# Opto_sensor_Comperator.net
KiCad netlist of a schematic drawn in EasyEDA
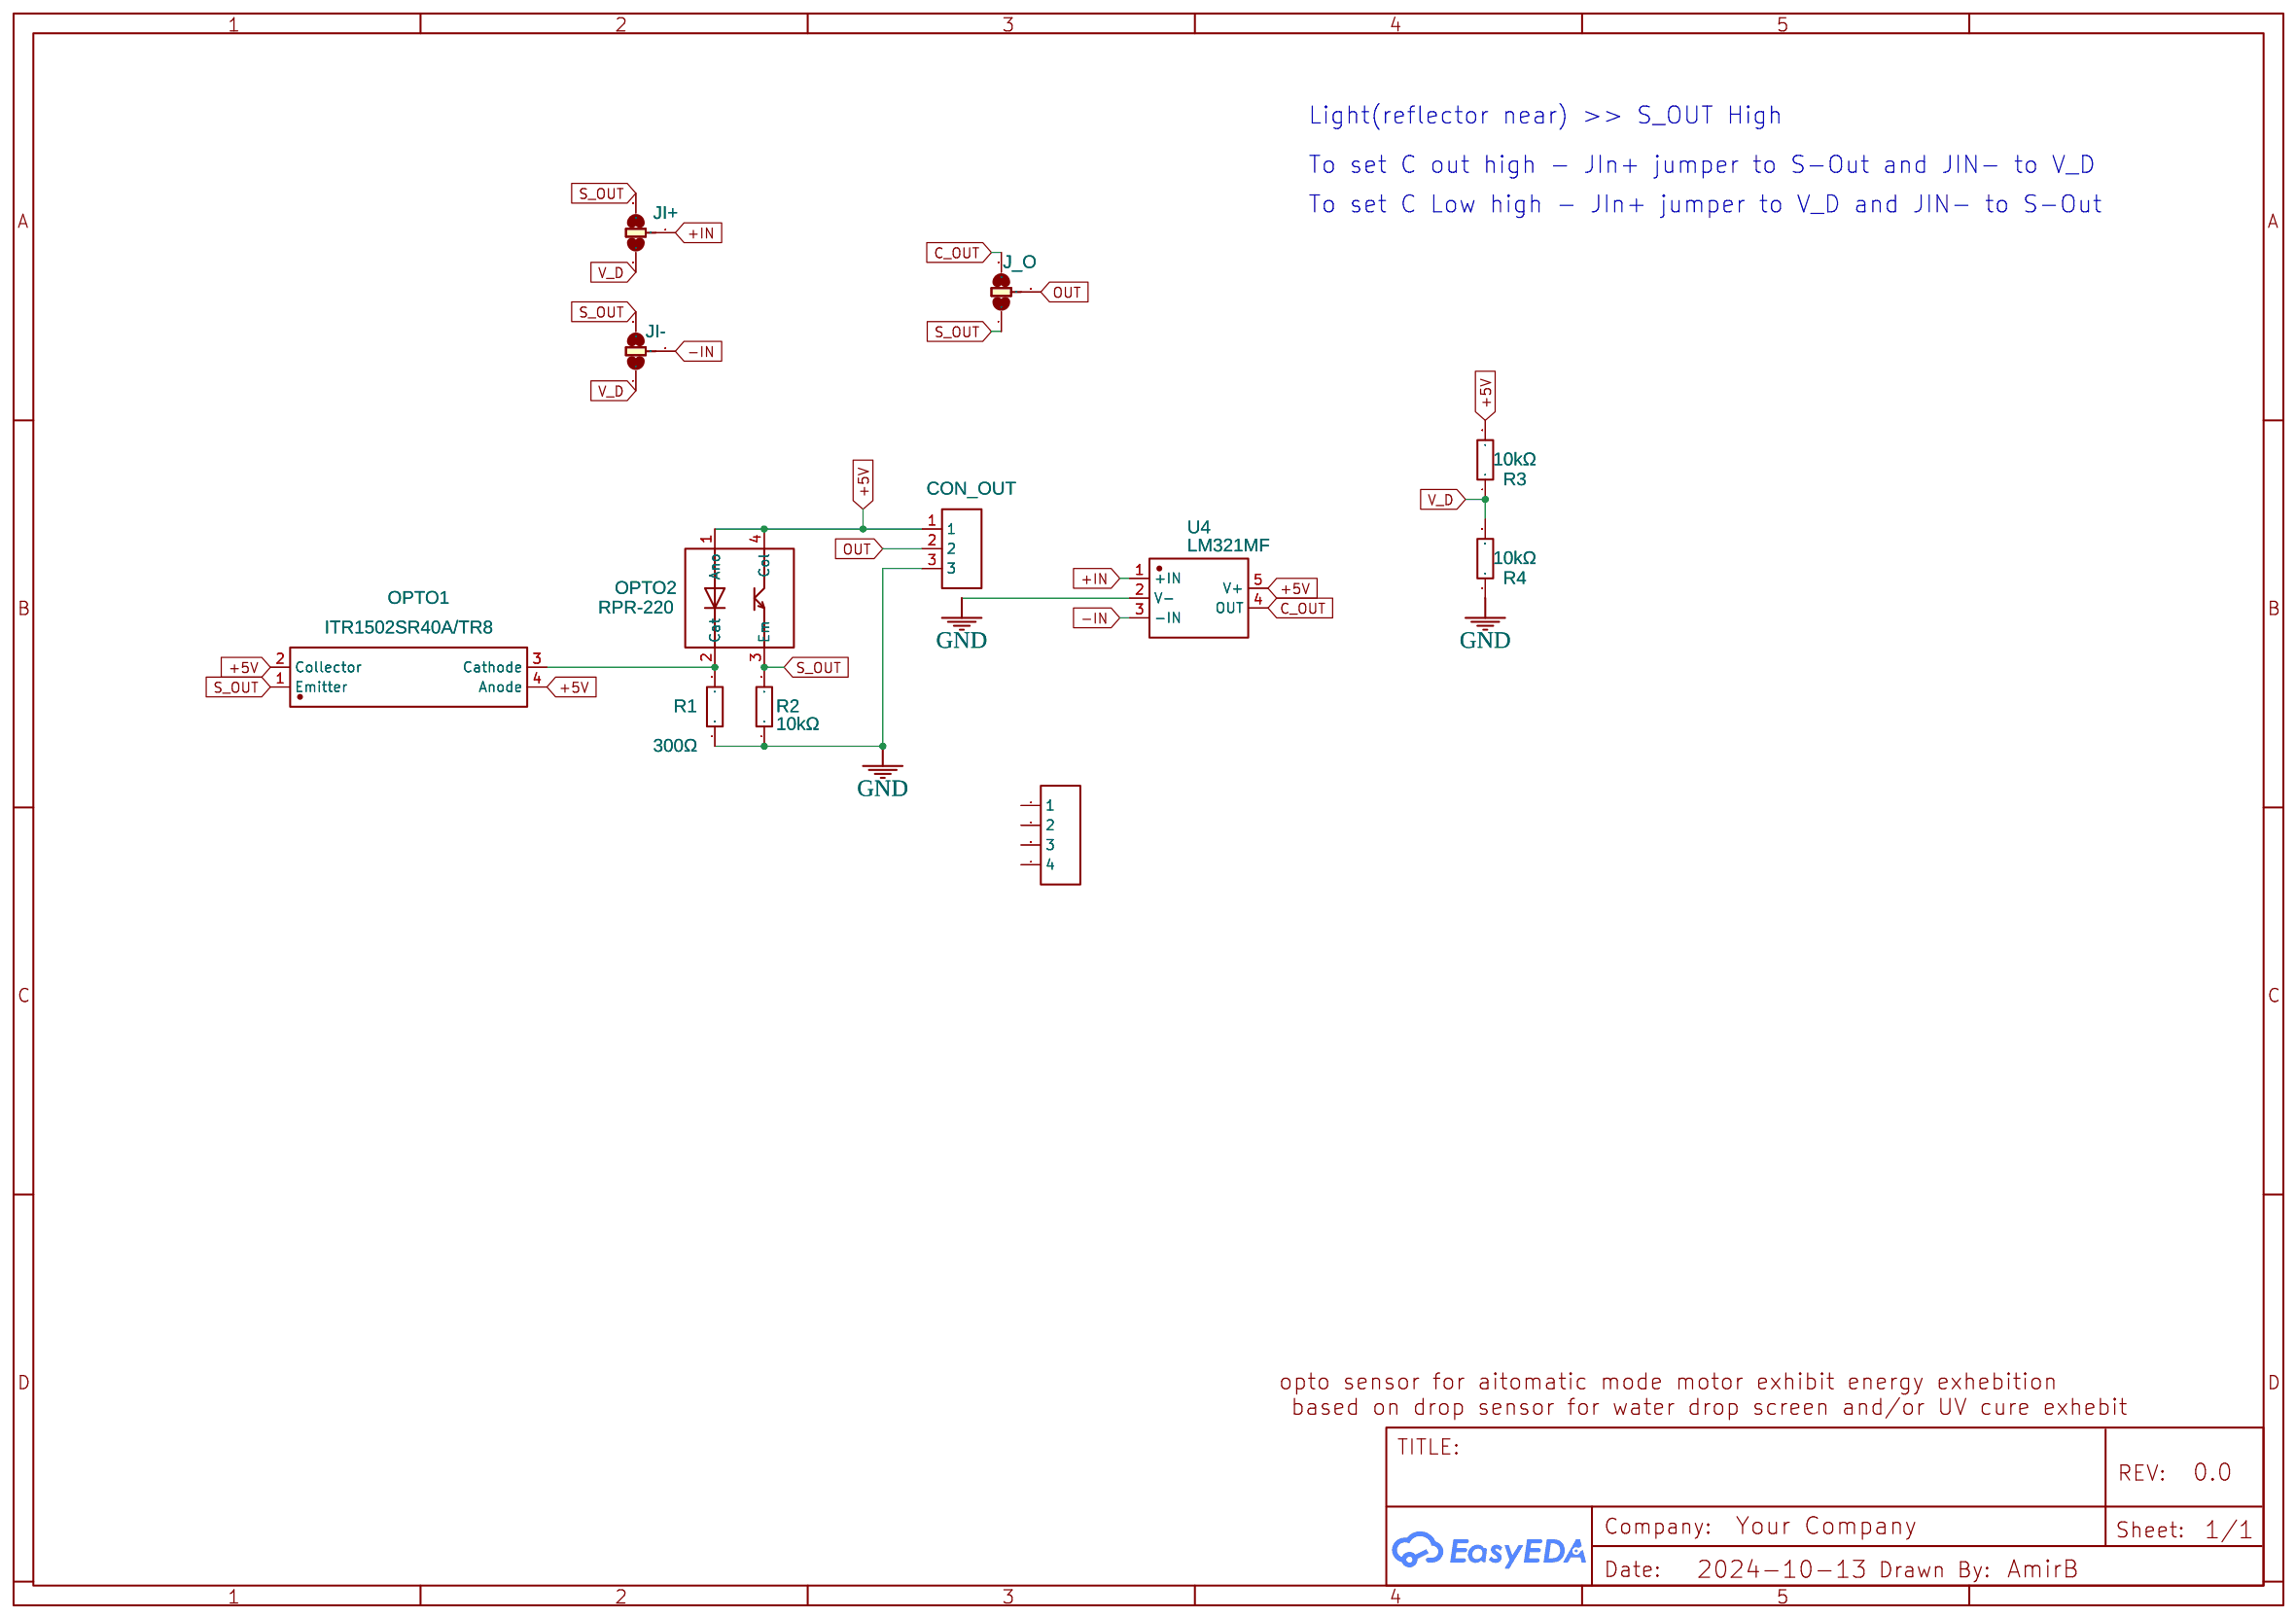
[diagram p0: schematic sheet]

(export (version "E")
  (design (tool "Eeschema 10.0.6"))
  (components
    (comp (ref "CON_OUT")
      (value "FK2510")
      (fields (field (name "Manufacturer Part") "2510-3A") (field (name "Manufacturer") "BOOMELE(博穆精密)"))
      (libsource (lib "") (part "kf2510_3A"))
    )
    (comp (ref "J1")
      (value "HDR-M-2.54_1x4")
      (fields (field (name "BOM_Supplier Part") "C124378"))
      (libsource (lib "") (part "HDR-M-2.54_1x4"))
    )
    (comp (ref "JI+")
      (value "JUMPER-PAD-3-NOYES_SILK")
      (libsource (lib "") (part "JUMPER-PAD-3-NOYES_SILK_1"))
    )
    (comp (ref "JI-") (value "JUMPER-PAD-3-NOYES_SILK") (libsource (lib "") (part "JUMPER-PAD-3-NOYES_SILK")))
    (comp (ref "J_O")
      (value "JUMPER-PAD-3-NOYES_SILK")
      (libsource (lib "") (part "JUMPER-PAD-3-NOYES_SILK_2"))
    )
    (comp (ref "OPTO1")
      (value "ITR1502SR40A/TR8")
      (fields (field (name "Manufacturer") "EVERLIGHT(亿光)"))
      (libsource (lib "") (part "ITR1502SR40A/TR8"))
    )
    (comp (ref "OPTO2")
      (value "RPR-220")
      (fields (field (name "Manufacturer") "ROHM(罗姆)"))
      (libsource (lib "") (part "RPR-220"))
    )
    (comp (ref "R1")
      (value "300Ω")
      (fields
        (field (name "Manufacturer Part") "0603WAF3000T5E")
        (field (name "Manufacturer") "UNI-ROYAL(厚声)")
      )
      (libsource (lib "") (part "0603WAF3000T5E"))
    )
    (comp (ref "R2")
      (value "10kΩ")
      (fields
        (field (name "Manufacturer Part") "0603WAF1002T5E")
        (field (name "Manufacturer") "UNI-ROYAL(厚声)")
      )
      (libsource (lib "") (part "0603WAF1002T5E"))
    )
    (comp (ref "R3")
      (value "10kΩ")
      (fields
        (field (name "Manufacturer Part") "0603WAF1002T5E")
        (field (name "Manufacturer") "UNI-ROYAL(厚声)")
      )
      (libsource (lib "") (part "0603WAF1002T5E"))
    )
    (comp (ref "R4")
      (value "10kΩ")
      (fields
        (field (name "Manufacturer Part") "0603WAF1002T5E")
        (field (name "Manufacturer") "UNI-ROYAL(厚声)")
      )
      (libsource (lib "") (part "0603WAF1002T5E"))
    )
    (comp (ref "U4")
      (value "LM321MF")
      (fields (field (name "Manufacturer") "UMW(友台半导体)"))
      (libsource (lib "") (part "LM321MF"))
    )
  )
  (nets
    (net (code "1") (name "+5V") (class "Default")
      (node (ref "CON_OUT") (pin "1") (pinfunction "1_1") (pintype "unspecified"))
      (node (ref "OPTO1") (pin "2") (pinfunction "Collector_2") (pintype "unspecified"))
      (node (ref "OPTO1") (pin "4") (pinfunction "Anode_4") (pintype "unspecified"))
      (node (ref "OPTO2") (pin "1") (pinfunction "Ano_1") (pintype "unspecified"))
      (node (ref "OPTO2") (pin "4") (pinfunction "Col_4") (pintype "unspecified"))
      (node (ref "R3") (pin "2") (pinfunction "2_2") (pintype "input"))
      (node (ref "U4") (pin "5") (pinfunction "V+_5") (pintype "unspecified"))
    )
    (net (code "2") (name "+IN") (class "Default")
      (node (ref "JI+") (pin "2") (pinfunction "2_2") (pintype "unspecified"))
      (node (ref "U4") (pin "1") (pinfunction "+IN_1") (pintype "unspecified"))
    )
    (net (code "3") (name "-IN") (class "Default")
      (node (ref "JI-") (pin "2") (pinfunction "2_2") (pintype "unspecified"))
      (node (ref "U4") (pin "3") (pinfunction "-IN_3") (pintype "unspecified"))
    )
    (net (code "4") (name "C_OUT") (class "Default")
      (node (ref "J_O") (pin "3") (pinfunction "3_3") (pintype "unspecified"))
      (node (ref "U4") (pin "4") (pinfunction "OUT_4") (pintype "unspecified"))
    )
    (net (code "5") (name "GND") (class "Default")
      (node (ref "CON_OUT") (pin "3") (pinfunction "3_3") (pintype "unspecified"))
      (node (ref "R1") (pin "1") (pinfunction "1_1") (pintype "input"))
      (node (ref "R2") (pin "1") (pinfunction "1_1") (pintype "input"))
      (node (ref "R4") (pin "1") (pinfunction "1_1") (pintype "input"))
      (node (ref "U4") (pin "2") (pinfunction "V-_2") (pintype "unspecified"))
    )
    (net (code "6") (name "Net-(OPTO1-Cathode)") (class "Default")
      (node (ref "OPTO1") (pin "3") (pinfunction "Cathode_3") (pintype "unspecified"))
      (node (ref "OPTO2") (pin "2") (pinfunction "Cat_2") (pintype "unspecified"))
      (node (ref "R1") (pin "2") (pinfunction "2_2") (pintype "input"))
    )
    (net (code "7") (name "OUT") (class "Default")
      (node (ref "CON_OUT") (pin "2") (pinfunction "2_2") (pintype "unspecified"))
      (node (ref "J_O") (pin "2") (pinfunction "2_2") (pintype "unspecified"))
    )
    (net (code "8") (name "S_OUT") (class "Default")
      (node (ref "JI+") (pin "3") (pinfunction "3_3") (pintype "unspecified"))
      (node (ref "JI-") (pin "3") (pinfunction "3_3") (pintype "unspecified"))
      (node (ref "J_O") (pin "1") (pinfunction "1_1") (pintype "unspecified"))
      (node (ref "OPTO1") (pin "1") (pinfunction "Emitter_1") (pintype "unspecified"))
      (node (ref "OPTO2") (pin "3") (pinfunction "Em_3") (pintype "unspecified"))
      (node (ref "R2") (pin "2") (pinfunction "2_2") (pintype "input"))
    )
    (net (code "9") (name "V_D") (class "Default")
      (node (ref "JI+") (pin "1") (pinfunction "1_1") (pintype "unspecified"))
      (node (ref "JI-") (pin "1") (pinfunction "1_1") (pintype "unspecified"))
      (node (ref "R3") (pin "1") (pinfunction "1_1") (pintype "input"))
      (node (ref "R4") (pin "2") (pinfunction "2_2") (pintype "input"))
    )
    (net (code "10") (name "unconnected-(J1-Pad1)") (class "Default")
      (node (ref "J1") (pin "1") (pinfunction "1_1") (pintype "unspecified"))
    )
    (net (code "11") (name "unconnected-(J1-Pad2)") (class "Default")
      (node (ref "J1") (pin "2") (pinfunction "2_2") (pintype "unspecified"))
    )
    (net (code "12") (name "unconnected-(J1-Pad3)") (class "Default")
      (node (ref "J1") (pin "3") (pinfunction "3_3") (pintype "unspecified"))
    )
    (net (code "13") (name "unconnected-(J1-Pad4)") (class "Default")
      (node (ref "J1") (pin "4") (pinfunction "4_4") (pintype "unspecified"))
    )
  )
)
